# Interface.net
KiCad netlist of a schematic drawn in Altium Designer
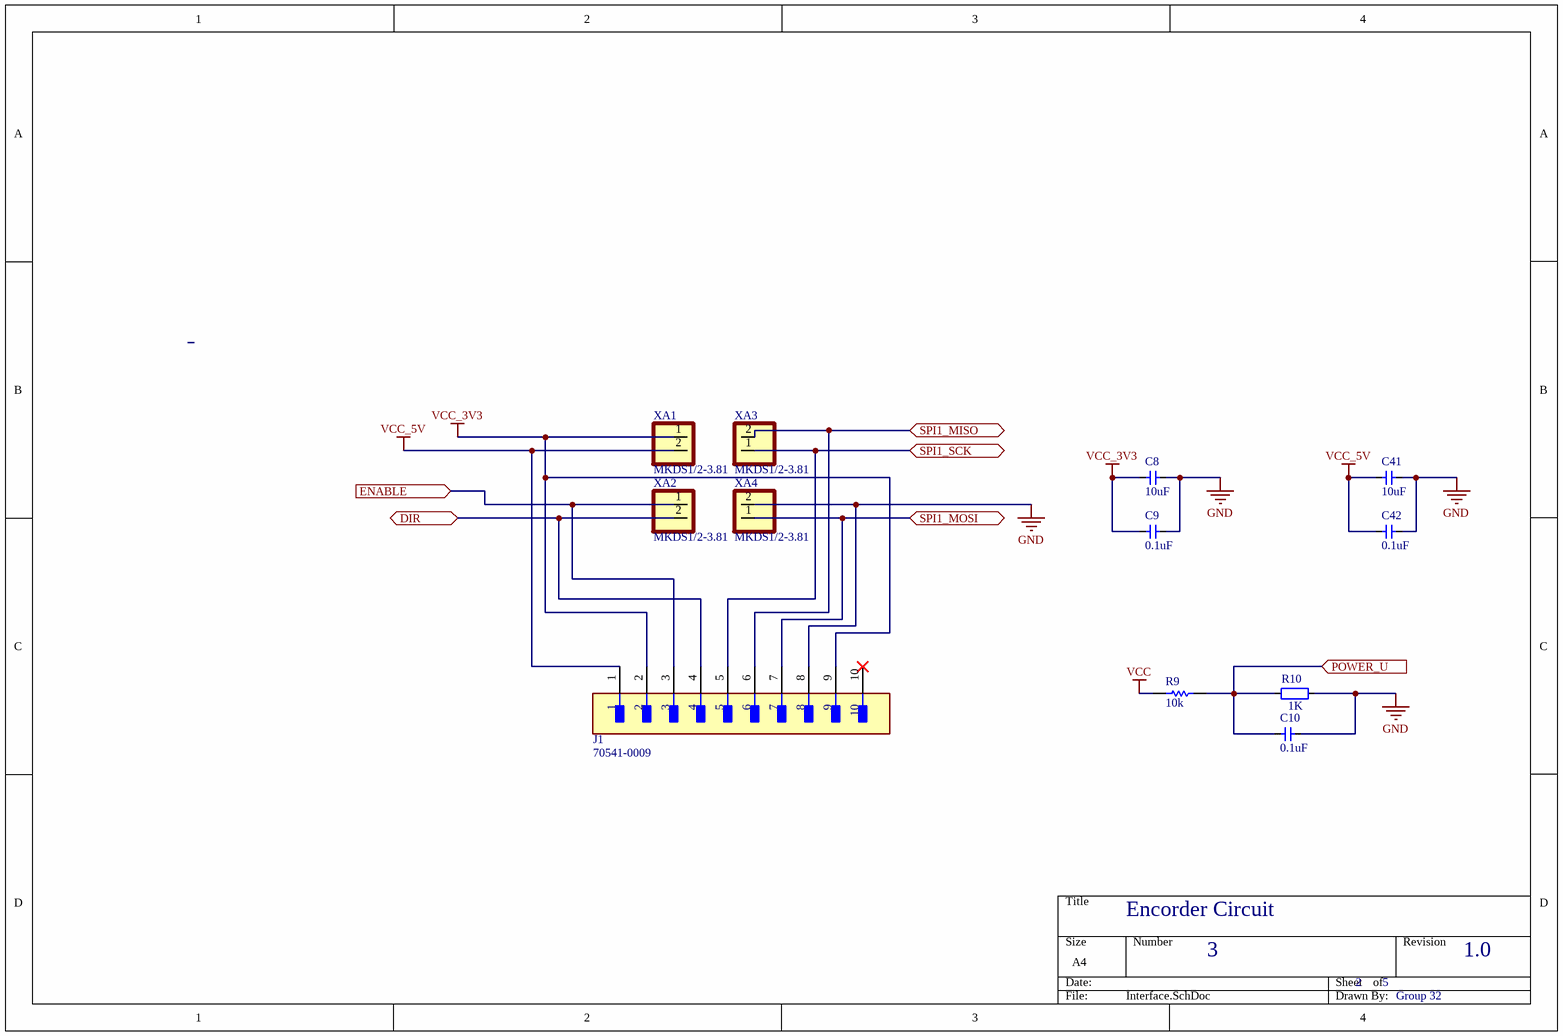
[diagram p0: Interface.SchDoc]

(export (version "E")
  (design (tool "Eeschema 10.0.6"))
  (components
    (comp (ref "C8")
      (value "10uF")
      (footprint "CAPC2013X94X50LL20T25")
      (description "Capacitor")
      (libsource (lib "MyPcbLib") (part "电容-0402"))
    )
    (comp (ref "C9")
      (value "0.1uF")
      (footprint "CAPC2013X94X50LL20T25")
      (description "Capacitor")
      (libsource (lib "MyPcbLib") (part "电容-0402"))
    )
    (comp (ref "C10")
      (value "0.1uF")
      (footprint "CAPC2013X94X50LL20T25")
      (description "Capacitor")
      (libsource (lib "MyPcbLib") (part "电容-0402"))
    )
    (comp (ref "C41")
      (value "10uF")
      (footprint "CAPC2013X94X50LL20T25")
      (description "Capacitor")
      (libsource (lib "MyPcbLib") (part "电容-0402"))
    )
    (comp (ref "C42")
      (value "0.1uF")
      (footprint "CAPC2013X94X50LL20T25")
      (description "Capacitor")
      (libsource (lib "MyPcbLib") (part "电容-0402"))
    )
    (comp (ref "J1")
      (value "70541-0009")
      (footprint "FP-70541-0009-MFG")
      (description "CONN HEADER VERT 10POS 2.54MM")
      (libsource (lib "Altium Content Vault") (part "aee40dc8b284c03a16094555aa210be"))
    )
    (comp (ref "R9")
      (value "RC0805FR-0710KL")
      (footprint "RESC2013X60X35NL10T20")
      (description "Chip Resistor, 10 KOhm, +/- 1%, 0.125 W, -55 to 155 degC, 0805 (2012 Metric), RoHS, Tape and Reel")
      (fields (field (name "MANUFACTURER") "Yageo") (field (name "RES") "10k"))
      (libsource (lib "Altium Content Vault") (part "RES-2"))
    )
    (comp (ref "R10")
      (value "1K")
      (footprint "RESC3116X65N")
      (description "Resistor")
      (libsource (lib "MyPcbLib") (part "电阻-0402"))
    )
    (comp (ref "XA1")
      (value "MKDS1/2-3.81")
      (footprint "PHOENIX_MKDS1/2-3.81 - duplicate")
      (description "2 Position Wire to Board Terminal Block Horizontal with Board 0.150 _3.81mm_ Through Hole")
      (fields (field (name "MF") "Phoenix Contact") (field (name "MP") "MKDS 1/ 2-3.81"))
      (libsource (lib "") (part "MKDS1/2-3.81_1"))
    )
    (comp (ref "XA2")
      (value "MKDS1/2-3.81")
      (footprint "PHOENIX_MKDS1/2-3.81 - duplicate")
      (description "2 Position Wire to Board Terminal Block Horizontal with Board 0.150 _3.81mm_ Through Hole")
      (fields (field (name "MF") "Phoenix Contact") (field (name "MP") "MKDS 1/ 2-3.81"))
      (libsource (lib "") (part "MKDS1/2-3.81_1"))
    )
    (comp (ref "XA3")
      (value "MKDS1/2-3.81")
      (footprint "PHOENIX_MKDS1/2-3.81 - duplicate")
      (description "2 Position Wire to Board Terminal Block Horizontal with Board 0.150 _3.81mm_ Through Hole")
      (fields (field (name "MF") "Phoenix Contact") (field (name "MP") "MKDS 1/ 2-3.81"))
      (libsource (lib "Schlib1") (part "MKDS1/2-3.81"))
    )
    (comp (ref "XA4")
      (value "MKDS1/2-3.81")
      (footprint "PHOENIX_MKDS1/2-3.81 - duplicate")
      (description "2 Position Wire to Board Terminal Block Horizontal with Board 0.150 _3.81mm_ Through Hole")
      (fields (field (name "MF") "Phoenix Contact") (field (name "MP") "MKDS 1/ 2-3.81"))
      (libsource (lib "Schlib1") (part "MKDS1/2-3.81"))
    )
  )
  (nets
    (net (code "1") (name "/DIR") (class "Default")
      (node (ref "J1") (pin "4") (pinfunction "4_4") (pintype "passive"))
      (node (ref "XA2") (pin "2") (pinfunction "2_2") (pintype "passive"))
    )
    (net (code "2") (name "/ENABLE") (class "Default")
      (node (ref "J1") (pin "3") (pinfunction "3_3") (pintype "passive"))
      (node (ref "XA2") (pin "1") (pinfunction "1_1") (pintype "passive"))
    )
    (net (code "3") (name "/POWER_U") (class "Default")
      (node (ref "C10") (pin "2") (pinfunction "2_2") (pintype "passive"))
      (node (ref "R10") (pin "1") (pinfunction "1_1") (pintype "passive"))
      (node (ref "R9") (pin "2") (pinfunction "2_2") (pintype "passive"))
    )
    (net (code "4") (name "/SPI1_MISO") (class "Default")
      (node (ref "J1") (pin "6") (pinfunction "6_6") (pintype "passive"))
      (node (ref "XA3") (pin "2") (pinfunction "2_2") (pintype "passive"))
    )
    (net (code "5") (name "/SPI1_MOSI") (class "Default")
      (node (ref "J1") (pin "7") (pinfunction "7_7") (pintype "passive"))
      (node (ref "XA4") (pin "1") (pinfunction "1_1") (pintype "passive"))
    )
    (net (code "6") (name "/SPI1_SCK") (class "Default")
      (node (ref "J1") (pin "5") (pinfunction "5_5") (pintype "passive"))
      (node (ref "XA3") (pin "1") (pinfunction "1_1") (pintype "passive"))
    )
    (net (code "7") (name "GND") (class "Default")
      (node (ref "C10") (pin "1") (pinfunction "1_1") (pintype "passive"))
      (node (ref "C41") (pin "1") (pinfunction "1_1") (pintype "passive"))
      (node (ref "C42") (pin "1") (pinfunction "1_1") (pintype "passive"))
      (node (ref "C8") (pin "1") (pinfunction "1_1") (pintype "passive"))
      (node (ref "C9") (pin "1") (pinfunction "1_1") (pintype "passive"))
      (node (ref "J1") (pin "8") (pinfunction "8_8") (pintype "passive"))
      (node (ref "R10") (pin "2") (pinfunction "2_2") (pintype "passive"))
      (node (ref "XA4") (pin "2") (pinfunction "2_2") (pintype "passive"))
    )
    (net (code "8") (name "VCC") (class "Default")
      (node (ref "R9") (pin "1") (pinfunction "1_1") (pintype "passive"))
    )
    (net (code "9") (name "VCC_3V3") (class "Default")
      (node (ref "C8") (pin "2") (pinfunction "2_2") (pintype "passive"))
      (node (ref "C9") (pin "2") (pinfunction "2_2") (pintype "passive"))
      (node (ref "J1") (pin "2") (pinfunction "2_2") (pintype "passive"))
      (node (ref "J1") (pin "9") (pinfunction "9_9") (pintype "passive"))
      (node (ref "XA1") (pin "1") (pinfunction "1_1") (pintype "passive"))
    )
    (net (code "10") (name "VCC_5V") (class "Default")
      (node (ref "C41") (pin "2") (pinfunction "2_2") (pintype "passive"))
      (node (ref "C42") (pin "2") (pinfunction "2_2") (pintype "passive"))
      (node (ref "J1") (pin "1") (pinfunction "1_1") (pintype "passive"))
      (node (ref "XA1") (pin "2") (pinfunction "2_2") (pintype "passive"))
    )
    (net (code "11") (name "unconnected-(J1-Pad10)") (class "Default")
      (node (ref "J1") (pin "10") (pinfunction "10_10") (pintype "passive+no_connect"))
    )
  )
)
